# Talko_1_0.net
KiCad netlist of a schematic drawn in EAGLE
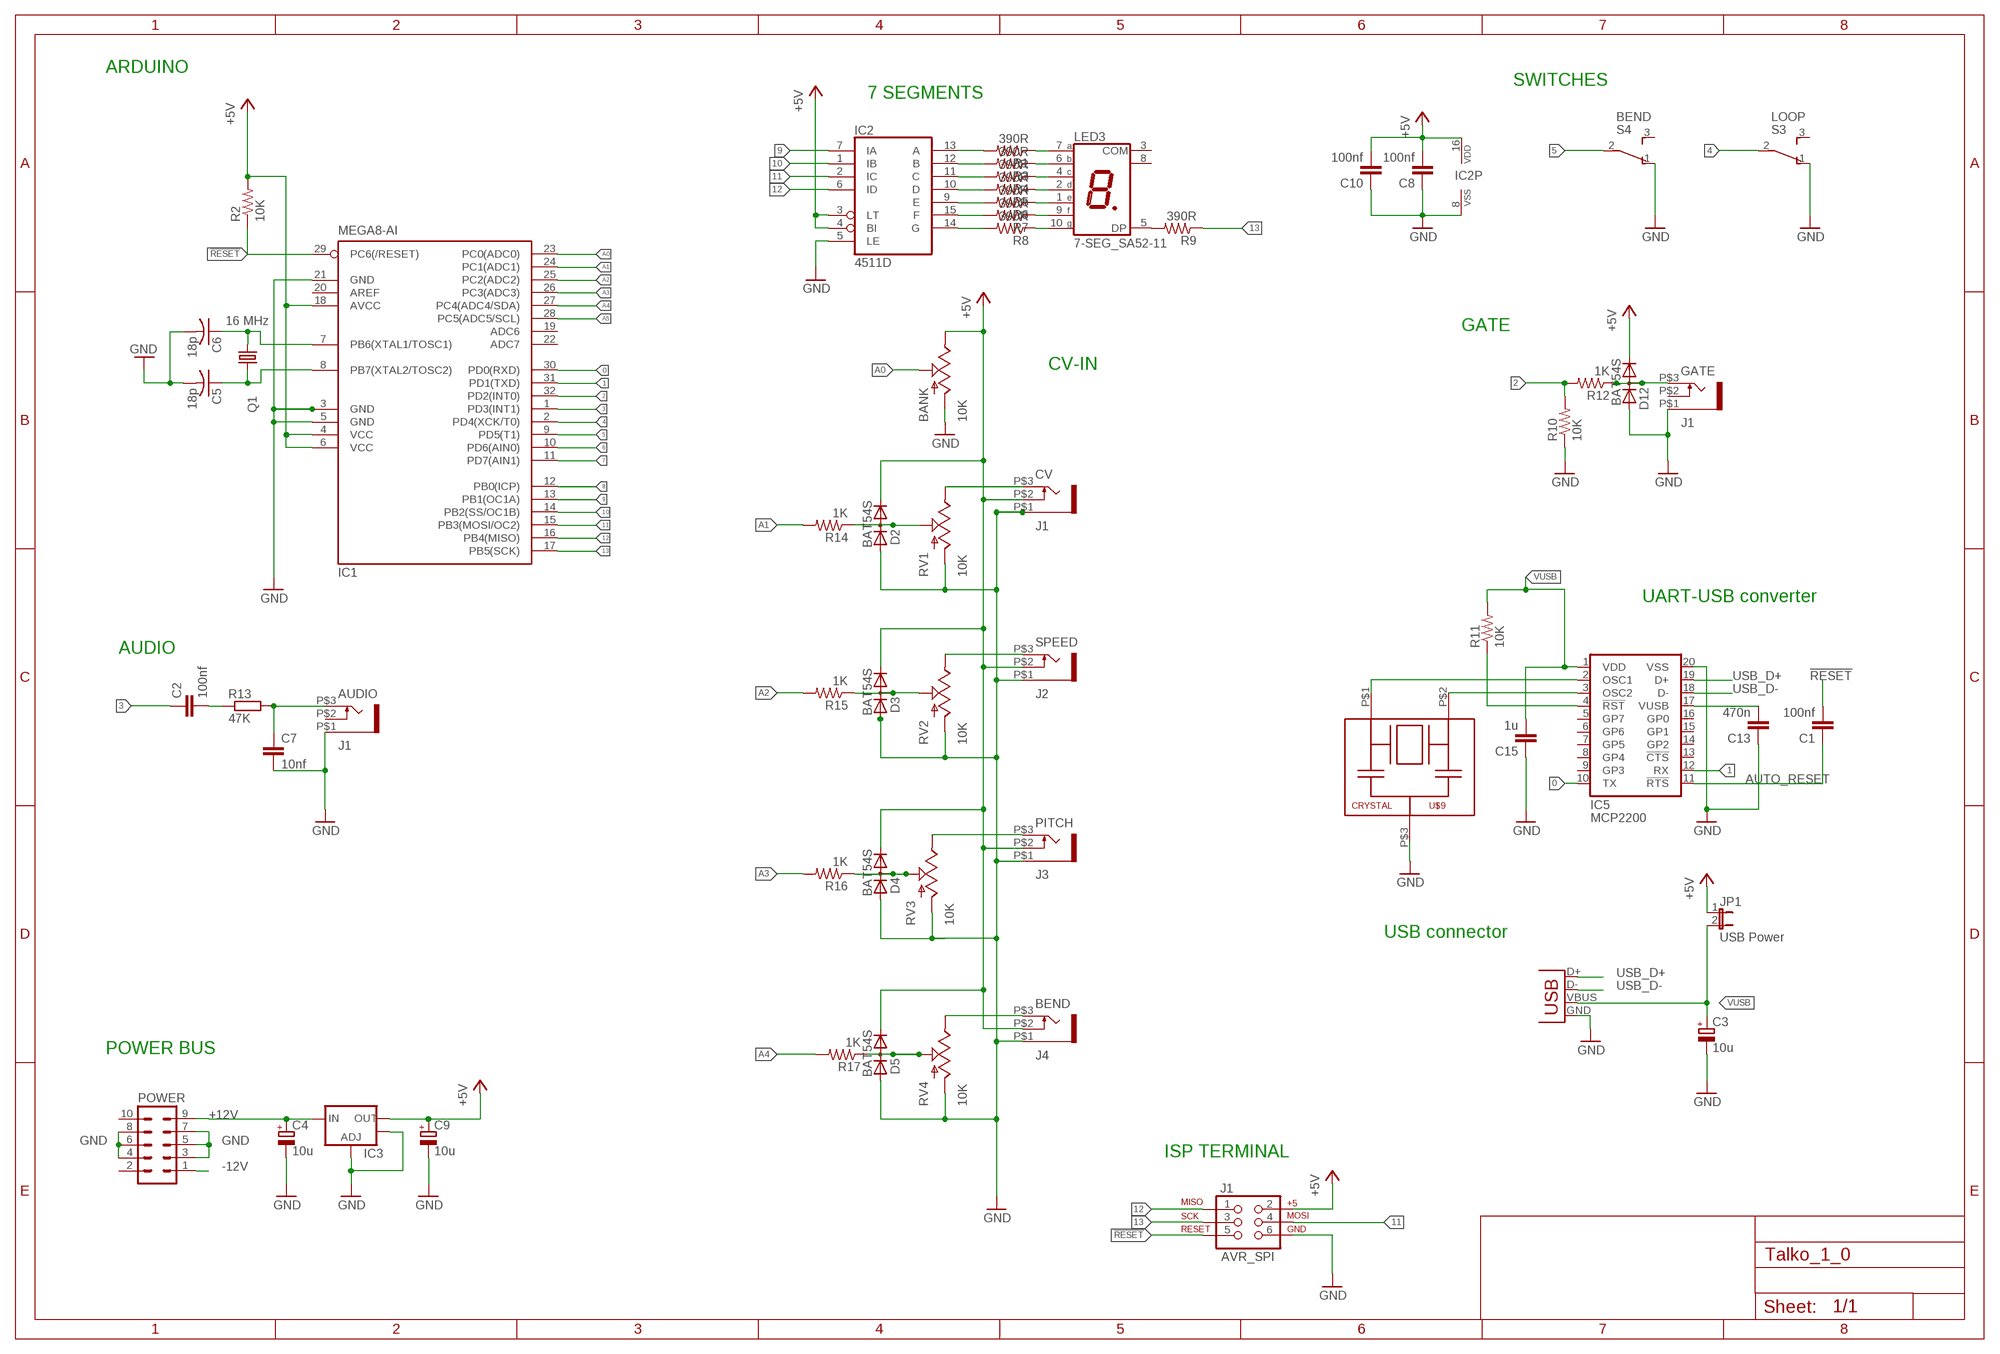
[diagram p0: schematic, sheet 1]

(export (version "E")
  (design (tool "Eeschema 10.0.6"))
  (components
    (comp (ref "AUDIO")
      (value "J1")
      (footprint "eagle-import:THONKICONN")
      (libsource (lib "eagle-import") (part "THONKICONN"))
    )
    (comp (ref "BANK")
      (value "10K")
      (footprint "eagle-import:ALPS_POT")
      (libsource (lib "eagle-import") (part "POT"))
    )
    (comp (ref "BEND")
      (value "J4")
      (footprint "eagle-import:THONKICONN")
      (libsource (lib "eagle-import") (part "THONKICONN"))
    )
    (comp (ref "C1")
      (value "100nf")
      (footprint "eagle-import:C0805")
      (libsource (lib "eagle-import") (part "C-EUC0805"))
    )
    (comp (ref "C2")
      (value "100nf")
      (footprint "eagle-import:C0805")
      (libsource (lib "eagle-import") (part "C-EUC0805"))
    )
    (comp (ref "C3")
      (value "10u")
      (footprint "eagle-import:R_2012-12R")
      (libsource (lib "eagle-import") (part "CPOL-EUR/2012-12R"))
    )
    (comp (ref "C4")
      (value "10u")
      (footprint "eagle-import:R_2012-12R")
      (libsource (lib "eagle-import") (part "CPOL-EUR/2012-12R"))
    )
    (comp (ref "C5")
      (value "18p")
      (footprint "eagle-import:C0805K")
      (libsource (lib "eagle-import") (part "C-USC0805K"))
    )
    (comp (ref "C6")
      (value "18p")
      (footprint "eagle-import:C0805K")
      (libsource (lib "eagle-import") (part "C-USC0805K"))
    )
    (comp (ref "C7")
      (value "10nf")
      (footprint "eagle-import:C0805")
      (libsource (lib "eagle-import") (part "C-EUC0805"))
    )
    (comp (ref "C8")
      (value "100nf")
      (footprint "eagle-import:C0805")
      (libsource (lib "eagle-import") (part "C-EUC0805"))
    )
    (comp (ref "C9")
      (value "10u")
      (footprint "eagle-import:R_2012-12R")
      (libsource (lib "eagle-import") (part "CPOL-EUR/2012-12R"))
    )
    (comp (ref "C10")
      (value "100nf")
      (footprint "eagle-import:C0805")
      (libsource (lib "eagle-import") (part "C-EUC0805"))
    )
    (comp (ref "C13")
      (value "470n")
      (footprint "eagle-import:0805")
      (libsource (lib "eagle-import") (part "CAP0805"))
    )
    (comp (ref "C15")
      (value "1u")
      (footprint "eagle-import:0805")
      (libsource (lib "eagle-import") (part "CAP0805"))
    )
    (comp (ref "CV")
      (value "J1")
      (footprint "eagle-import:THONKICONN")
      (libsource (lib "eagle-import") (part "THONKICONN"))
    )
    (comp (ref "D2")
      (value "BAT54S")
      (footprint "eagle-import:SOT23")
      (libsource (lib "eagle-import") (part "DIODE_2CACA-SOT23"))
    )
    (comp (ref "D3")
      (value "BAT54S")
      (footprint "eagle-import:SOT23")
      (libsource (lib "eagle-import") (part "DIODE_2CACA-SOT23"))
    )
    (comp (ref "D4")
      (value "BAT54S")
      (footprint "eagle-import:SOT23")
      (libsource (lib "eagle-import") (part "DIODE_2CACA-SOT23"))
    )
    (comp (ref "D5")
      (value "BAT54S")
      (footprint "eagle-import:SOT23")
      (libsource (lib "eagle-import") (part "DIODE_2CACA-SOT23"))
    )
    (comp (ref "D12")
      (value "BAT54S")
      (footprint "eagle-import:SOT23")
      (libsource (lib "eagle-import") (part "DIODE_2CACA-SOT23"))
    )
    (comp (ref "GATE")
      (value "J1")
      (footprint "eagle-import:THONKICONN")
      (libsource (lib "eagle-import") (part "THONKICONN"))
    )
    (comp (ref "IC1")
      (value "MEGA8-AI")
      (footprint "eagle-import:TQFP32-08")
      (fields (field (name "MPN") "ATMEGA8-16AU"))
      (libsource (lib "eagle-import") (part "MEGA8-AI"))
    )
    (comp (ref "IC2")
      (value "4511D")
      (footprint "eagle-import:SO16")
      (fields (field (name "OC_MOUSER") "863-MC14511BDG"))
      (libsource (lib "eagle-import") (part "4511D"))
    )
    (comp (ref "IC3")
      (value "V_REG_LM1117SOT223")
      (footprint "eagle-import:SOT223")
      (libsource (lib "eagle-import") (part "V_REG_LM1117SOT223"))
    )
    (comp (ref "IC5")
      (value "MCP2200")
      (footprint "eagle-import:SO20")
      (libsource (lib "eagle-import") (part "MCP2200"))
    )
    (comp (ref "J1")
      (value "AVR_SPI")
      (footprint "eagle-import:2X3_LOCK")
      (libsource (lib "eagle-import") (part "AVR_SPI_PRG_62X3_LOCK"))
    )
    (comp (ref "JP1")
      (value "USB Power")
      (footprint "eagle-import:JP1")
      (libsource (lib "eagle-import") (part "JP1E"))
    )
    (comp (ref "LED3")
      (value "7-SEG_SA52-11")
      (footprint "eagle-import:SA52-11")
      (fields (field (name "OC_FARNELL") "1168602"))
      (libsource (lib "eagle-import") (part "7-SEG_SA52-11"))
    )
    (comp (ref "PITCH")
      (value "J3")
      (footprint "eagle-import:THONKICONN")
      (libsource (lib "eagle-import") (part "THONKICONN"))
    )
    (comp (ref "POWER")
      (value "10_PIN_HEADER")
      (footprint "eagle-import:MA05-2")
      (libsource (lib "eagle-import") (part "10_PIN_HEADER"))
    )
    (comp (ref "Q1")
      (value "16 MHz")
      (footprint "eagle-import:CTS406")
      (libsource (lib "eagle-import") (part "CRYSTALCTS406"))
    )
    (comp (ref "R1")
      (value "390R")
      (footprint "eagle-import:M0805")
      (libsource (lib "eagle-import") (part "R-US_M0805"))
    )
    (comp (ref "R2")
      (value "10K")
      (footprint "eagle-import:M0805")
      (libsource (lib "eagle-import") (part "R-US_M0805"))
    )
    (comp (ref "R3")
      (value "390R")
      (footprint "eagle-import:M0805")
      (libsource (lib "eagle-import") (part "R-US_M0805"))
    )
    (comp (ref "R4")
      (value "390R")
      (footprint "eagle-import:M0805")
      (libsource (lib "eagle-import") (part "R-US_M0805"))
    )
    (comp (ref "R5")
      (value "390R")
      (footprint "eagle-import:M0805")
      (libsource (lib "eagle-import") (part "R-US_M0805"))
    )
    (comp (ref "R6")
      (value "390R")
      (footprint "eagle-import:M0805")
      (libsource (lib "eagle-import") (part "R-US_M0805"))
    )
    (comp (ref "R7")
      (value "390R")
      (footprint "eagle-import:M0805")
      (libsource (lib "eagle-import") (part "R-US_M0805"))
    )
    (comp (ref "R8")
      (value "390R")
      (footprint "eagle-import:M0805")
      (libsource (lib "eagle-import") (part "R-US_M0805"))
    )
    (comp (ref "R9")
      (value "390R")
      (footprint "eagle-import:M0805")
      (libsource (lib "eagle-import") (part "R-US_M0805"))
    )
    (comp (ref "R10")
      (value "10K")
      (footprint "eagle-import:M0805")
      (libsource (lib "eagle-import") (part "R-US_M0805"))
    )
    (comp (ref "R11")
      (value "10K")
      (footprint "eagle-import:M0805")
      (libsource (lib "eagle-import") (part "R-US_M0805"))
    )
    (comp (ref "R12")
      (value "1K")
      (footprint "eagle-import:M0805")
      (libsource (lib "eagle-import") (part "R-US_M0805"))
    )
    (comp (ref "R13")
      (value "47K")
      (footprint "eagle-import:M0805")
      (libsource (lib "eagle-import") (part "R-EU_M0805"))
    )
    (comp (ref "R14")
      (value "1K")
      (footprint "eagle-import:M0805")
      (libsource (lib "eagle-import") (part "R-US_M0805"))
    )
    (comp (ref "R15")
      (value "1K")
      (footprint "eagle-import:M0805")
      (libsource (lib "eagle-import") (part "R-US_M0805"))
    )
    (comp (ref "R16")
      (value "1K")
      (footprint "eagle-import:M0805")
      (libsource (lib "eagle-import") (part "R-US_M0805"))
    )
    (comp (ref "R17")
      (value "1K")
      (footprint "eagle-import:M0805")
      (libsource (lib "eagle-import") (part "R-US_M0805"))
    )
    (comp (ref "RV1")
      (value "10K")
      (footprint "eagle-import:ALPS_POT")
      (libsource (lib "eagle-import") (part "POT"))
    )
    (comp (ref "RV2")
      (value "10K")
      (footprint "eagle-import:ALPS_POT")
      (libsource (lib "eagle-import") (part "POT"))
    )
    (comp (ref "RV3")
      (value "10K")
      (footprint "eagle-import:ALPS_POT")
      (libsource (lib "eagle-import") (part "POT"))
    )
    (comp (ref "RV4")
      (value "10K")
      (footprint "eagle-import:ALPS_POT")
      (libsource (lib "eagle-import") (part "POT"))
    )
    (comp (ref "S3")
      (value "LOOP")
      (footprint "eagle-import:TL3XPO")
      (libsource (lib "eagle-import") (part "TL36PO"))
    )
    (comp (ref "S4")
      (value "BEND")
      (footprint "eagle-import:TL3XPO")
      (libsource (lib "eagle-import") (part "TL36PO"))
    )
    (comp (ref "SPEED")
      (value "J2")
      (footprint "eagle-import:THONKICONN")
      (libsource (lib "eagle-import") (part "THONKICONN"))
    )
    (comp (ref "U$9")
      (value "CRYSTAL")
      (footprint "eagle-import:CRYSTAL")
      (libsource (lib "eagle-import") (part "CRYSTAL"))
    )
    (comp (ref "X3")
      (value "USB")
      (footprint "eagle-import:USB-B-PTH-VERTICAL")
      (libsource (lib "eagle-import") (part "USBPTH-VERTICAL"))
    )
  )
  (nets
    (net (code "1") (name "+5V") (class "Default")
      (node (ref "BANK") (pin "P$1") (pinfunction "E_P$1") (pintype "passive"))
      (node (ref "BEND") (pin "P$2") (pinfunction "4_P$2") (pintype "passive"))
      (node (ref "C10") (pin "2") (pinfunction "2_2") (pintype "passive"))
      (node (ref "C8") (pin "2") (pinfunction "2_2") (pintype "passive"))
      (node (ref "C9") (pin "+") (pinfunction "+_+") (pintype "passive"))
      (node (ref "CV") (pin "P$2") (pinfunction "4_P$2") (pintype "passive"))
      (node (ref "D12") (pin "2") (pinfunction "C_2") (pintype "passive"))
      (node (ref "D2") (pin "2") (pinfunction "C_2") (pintype "passive"))
      (node (ref "D3") (pin "2") (pinfunction "C_2") (pintype "passive"))
      (node (ref "D4") (pin "2") (pinfunction "C_2") (pintype "passive"))
      (node (ref "D5") (pin "2") (pinfunction "C_2") (pintype "passive"))
      (node (ref "IC1") (pin "18") (pinfunction "AVCC_18") (pintype "power_in"))
      (node (ref "IC1") (pin "4") (pinfunction "VCC_4") (pintype "power_in"))
      (node (ref "IC1") (pin "6") (pinfunction "VCC_6") (pintype "power_in"))
      (node (ref "IC2") (pin "16") (pinfunction "VDD_16") (pintype "power_in"))
      (node (ref "IC2") (pin "3") (pinfunction "LT_3") (pintype "input"))
      (node (ref "IC2") (pin "4") (pinfunction "BI_4") (pintype "input"))
      (node (ref "IC3") (pin "2") (pinfunction "OUT_2") (pintype "output"))
      (node (ref "J1") (pin "2") (pinfunction "2_2") (pintype "passive"))
      (node (ref "JP1") (pin "1") (pinfunction "1_1") (pintype "passive"))
      (node (ref "PITCH") (pin "P$2") (pinfunction "4_P$2") (pintype "passive"))
      (node (ref "R2") (pin "2") (pinfunction "2_2") (pintype "passive"))
      (node (ref "SPEED") (pin "P$2") (pinfunction "4_P$2") (pintype "passive"))
    )
    (net (code "2") (name "/+12V") (class "Default")
      (node (ref "C4") (pin "+") (pinfunction "+_+") (pintype "passive"))
      (node (ref "IC3") (pin "3") (pinfunction "IN_3") (pintype "input"))
      (node (ref "POWER") (pin "9") (pinfunction "9_9") (pintype "passive"))
    )
    (net (code "3") (name "/-12V") (class "Default")
      (node (ref "POWER") (pin "1") (pinfunction "1_1") (pintype "passive"))
    )
    (net (code "4") (name "/AUTO_RESET") (class "Default")
      (node (ref "C1") (pin "1") (pinfunction "1_1") (pintype "passive"))
      (node (ref "IC5") (pin "11") (pinfunction "~{RTS}_11") (pintype "bidirectional"))
    )
    (net (code "5") (name "/USB_D+") (class "Default")
      (node (ref "IC5") (pin "19") (pinfunction "D+_19") (pintype "bidirectional"))
      (node (ref "X3") (pin "D+") (pinfunction "D+_D+") (pintype "bidirectional"))
    )
    (net (code "6") (name "/USB_D-") (class "Default")
      (node (ref "IC5") (pin "18") (pinfunction "D-_18") (pintype "bidirectional"))
      (node (ref "X3") (pin "D-") (pinfunction "D-_D-") (pintype "bidirectional"))
    )
    (net (code "7") (name "/~{RESET}") (class "Default")
      (node (ref "C1") (pin "2") (pinfunction "2_2") (pintype "passive"))
      (node (ref "IC1") (pin "29") (pinfunction "PC6(/RESET)_29") (pintype "bidirectional"))
      (node (ref "J1") (pin "5") (pinfunction "5_5") (pintype "passive"))
      (node (ref "R2") (pin "1") (pinfunction "1_1") (pintype "passive"))
    )
    (net (code "8") (name "0") (class "Default")
      (node (ref "IC1") (pin "30") (pinfunction "PD0(RXD)_30") (pintype "bidirectional"))
      (node (ref "IC5") (pin "10") (pinfunction "TX_10") (pintype "bidirectional"))
    )
    (net (code "9") (name "1") (class "Default")
      (node (ref "IC1") (pin "31") (pinfunction "PD1(TXD)_31") (pintype "bidirectional"))
      (node (ref "IC5") (pin "12") (pinfunction "RX_12") (pintype "bidirectional"))
    )
    (net (code "10") (name "2") (class "Default")
      (node (ref "IC1") (pin "32") (pinfunction "PD2(INT0)_32") (pintype "bidirectional"))
      (node (ref "R10") (pin "2") (pinfunction "2_2") (pintype "passive"))
      (node (ref "R12") (pin "2") (pinfunction "2_2") (pintype "passive"))
    )
    (net (code "11") (name "3") (class "Default")
      (node (ref "C2") (pin "1") (pinfunction "1_1") (pintype "passive"))
      (node (ref "IC1") (pin "1") (pinfunction "PD3(INT1)_1") (pintype "bidirectional"))
    )
    (net (code "12") (name "4") (class "Default")
      (node (ref "IC1") (pin "2") (pinfunction "PD4(XCK/T0)_2") (pintype "bidirectional"))
      (node (ref "S3") (pin "2") (pinfunction "P_2") (pintype "passive"))
    )
    (net (code "13") (name "5") (class "Default")
      (node (ref "IC1") (pin "9") (pinfunction "PD5(T1)_9") (pintype "bidirectional"))
      (node (ref "S4") (pin "2") (pinfunction "P_2") (pintype "passive"))
    )
    (net (code "14") (name "6") (class "Default")
      (node (ref "IC1") (pin "10") (pinfunction "PD6(AIN0)_10") (pintype "bidirectional"))
    )
    (net (code "15") (name "7") (class "Default")
      (node (ref "IC1") (pin "11") (pinfunction "PD7(AIN1)_11") (pintype "bidirectional"))
    )
    (net (code "16") (name "8") (class "Default")
      (node (ref "IC1") (pin "12") (pinfunction "PB0(ICP)_12") (pintype "bidirectional"))
    )
    (net (code "17") (name "9") (class "Default")
      (node (ref "IC1") (pin "13") (pinfunction "PB1(OC1A)_13") (pintype "bidirectional"))
      (node (ref "IC2") (pin "7") (pinfunction "IA_7") (pintype "input"))
    )
    (net (code "18") (name "10") (class "Default")
      (node (ref "IC1") (pin "14") (pinfunction "PB2(SS/OC1B)_14") (pintype "bidirectional"))
      (node (ref "IC2") (pin "1") (pinfunction "IB_1") (pintype "input"))
    )
    (net (code "19") (name "11") (class "Default")
      (node (ref "IC1") (pin "15") (pinfunction "PB3(MOSI/OC2)_15") (pintype "bidirectional"))
      (node (ref "IC2") (pin "2") (pinfunction "IC_2") (pintype "input"))
      (node (ref "J1") (pin "4") (pinfunction "4_4") (pintype "passive"))
    )
    (net (code "20") (name "12") (class "Default")
      (node (ref "IC1") (pin "16") (pinfunction "PB4(MISO)_16") (pintype "bidirectional"))
      (node (ref "IC2") (pin "6") (pinfunction "ID_6") (pintype "input"))
      (node (ref "J1") (pin "1") (pinfunction "1_1") (pintype "passive"))
    )
    (net (code "21") (name "13") (class "Default")
      (node (ref "IC1") (pin "17") (pinfunction "PB5(SCK)_17") (pintype "bidirectional"))
      (node (ref "J1") (pin "3") (pinfunction "3_3") (pintype "passive"))
      (node (ref "R9") (pin "1") (pinfunction "1_1") (pintype "passive"))
    )
    (net (code "22") (name "A0") (class "Default")
      (node (ref "BANK") (pin "P$2") (pinfunction "S_P$2") (pintype "passive"))
      (node (ref "IC1") (pin "23") (pinfunction "PC0(ADC0)_23") (pintype "bidirectional"))
    )
    (net (code "23") (name "A1") (class "Default")
      (node (ref "IC1") (pin "24") (pinfunction "PC1(ADC1)_24") (pintype "bidirectional"))
      (node (ref "R14") (pin "2") (pinfunction "2_2") (pintype "passive"))
    )
    (net (code "24") (name "A2") (class "Default")
      (node (ref "IC1") (pin "25") (pinfunction "PC2(ADC2)_25") (pintype "bidirectional"))
      (node (ref "R15") (pin "2") (pinfunction "2_2") (pintype "passive"))
    )
    (net (code "25") (name "A3") (class "Default")
      (node (ref "IC1") (pin "26") (pinfunction "PC3(ADC3)_26") (pintype "bidirectional"))
      (node (ref "R16") (pin "2") (pinfunction "2_2") (pintype "passive"))
    )
    (net (code "26") (name "A4") (class "Default")
      (node (ref "IC1") (pin "27") (pinfunction "PC4(ADC4/SDA)_27") (pintype "bidirectional"))
      (node (ref "R17") (pin "2") (pinfunction "2_2") (pintype "passive"))
    )
    (net (code "27") (name "A5") (class "Default")
      (node (ref "IC1") (pin "28") (pinfunction "PC5(ADC5/SCL)_28") (pintype "bidirectional"))
    )
    (net (code "28") (name "GND") (class "Default")
      (node (ref "AUDIO") (pin "P$1") (pinfunction "5_P$1") (pintype "passive"))
      (node (ref "BANK") (pin "P$3") (pinfunction "A_P$3") (pintype "passive"))
      (node (ref "BEND") (pin "P$1") (pinfunction "5_P$1") (pintype "passive"))
      (node (ref "C10") (pin "1") (pinfunction "1_1") (pintype "passive"))
      (node (ref "C13") (pin "1") (pinfunction "1_1") (pintype "passive"))
      (node (ref "C15") (pin "1") (pinfunction "1_1") (pintype "passive"))
      (node (ref "C3") (pin "-") (pinfunction "-_-") (pintype "passive"))
      (node (ref "C4") (pin "-") (pinfunction "-_-") (pintype "passive"))
      (node (ref "C5") (pin "2") (pinfunction "2_2") (pintype "passive"))
      (node (ref "C6") (pin "2") (pinfunction "2_2") (pintype "passive"))
      (node (ref "C7") (pin "2") (pinfunction "2_2") (pintype "passive"))
      (node (ref "C8") (pin "1") (pinfunction "1_1") (pintype "passive"))
      (node (ref "C9") (pin "-") (pinfunction "-_-") (pintype "passive"))
      (node (ref "CV") (pin "P$1") (pinfunction "5_P$1") (pintype "passive"))
      (node (ref "D12") (pin "1") (pinfunction "A_1") (pintype "passive"))
      (node (ref "D2") (pin "1") (pinfunction "A_1") (pintype "passive"))
      (node (ref "D3") (pin "1") (pinfunction "A_1") (pintype "passive"))
      (node (ref "D4") (pin "1") (pinfunction "A_1") (pintype "passive"))
      (node (ref "D5") (pin "1") (pinfunction "A_1") (pintype "passive"))
      (node (ref "GATE") (pin "P$1") (pinfunction "5_P$1") (pintype "passive"))
      (node (ref "IC1") (pin "21") (pinfunction "GND_21") (pintype "power_in"))
      (node (ref "IC1") (pin "3") (pinfunction "GND_3") (pintype "power_in"))
      (node (ref "IC1") (pin "5") (pinfunction "GND_5") (pintype "power_in"))
      (node (ref "IC2") (pin "5") (pinfunction "LE_5") (pintype "input"))
      (node (ref "IC2") (pin "8") (pinfunction "VSS_8") (pintype "power_in"))
      (node (ref "IC3") (pin "1") (pinfunction "ADJ_1") (pintype "input"))
      (node (ref "IC3") (pin "4") (pinfunction "OUT_4") (pintype "output"))
      (node (ref "IC5") (pin "20") (pinfunction "VSS_20") (pintype "power_in"))
      (node (ref "J1") (pin "6") (pinfunction "6_6") (pintype "passive"))
      (node (ref "PITCH") (pin "P$1") (pinfunction "5_P$1") (pintype "passive"))
      (node (ref "POWER") (pin "3") (pinfunction "3_3") (pintype "passive"))
      (node (ref "POWER") (pin "4") (pinfunction "4_4") (pintype "passive"))
      (node (ref "POWER") (pin "5") (pinfunction "5_5") (pintype "passive"))
      (node (ref "POWER") (pin "6") (pinfunction "6_6") (pintype "passive"))
      (node (ref "POWER") (pin "7") (pinfunction "7_7") (pintype "passive"))
      (node (ref "POWER") (pin "8") (pinfunction "8_8") (pintype "passive"))
      (node (ref "R10") (pin "1") (pinfunction "1_1") (pintype "passive"))
      (node (ref "RV1") (pin "P$3") (pinfunction "A_P$3") (pintype "passive"))
      (node (ref "RV2") (pin "P$3") (pinfunction "A_P$3") (pintype "passive"))
      (node (ref "RV3") (pin "P$3") (pinfunction "A_P$3") (pintype "passive"))
      (node (ref "RV4") (pin "P$3") (pinfunction "A_P$3") (pintype "passive"))
      (node (ref "S3") (pin "1") (pinfunction "O_1") (pintype "passive"))
      (node (ref "S4") (pin "1") (pinfunction "O_1") (pintype "passive"))
      (node (ref "SPEED") (pin "P$1") (pinfunction "5_P$1") (pintype "passive"))
      (node (ref "U$9") (pin "P$3") (pinfunction "3_P$3") (pintype "bidirectional"))
      (node (ref "X3") (pin "GND") (pinfunction "GND_GND") (pintype "bidirectional"))
    )
    (net (code "29") (name "Net-(AUDIO-3)") (class "Default")
      (node (ref "AUDIO") (pin "P$3") (pinfunction "3_P$3") (pintype "passive"))
      (node (ref "C7") (pin "1") (pinfunction "1_1") (pintype "passive"))
      (node (ref "R13") (pin "2") (pinfunction "2_2") (pintype "passive"))
    )
    (net (code "30") (name "Net-(BEND-3)") (class "Default")
      (node (ref "BEND") (pin "P$3") (pinfunction "3_P$3") (pintype "passive"))
      (node (ref "RV4") (pin "P$1") (pinfunction "E_P$1") (pintype "passive"))
    )
    (net (code "31") (name "Net-(C2-Pad2)") (class "Default")
      (node (ref "C2") (pin "2") (pinfunction "2_2") (pintype "passive"))
      (node (ref "R13") (pin "1") (pinfunction "1_1") (pintype "passive"))
    )
    (net (code "32") (name "Net-(CV-3)") (class "Default")
      (node (ref "CV") (pin "P$3") (pinfunction "3_P$3") (pintype "passive"))
      (node (ref "RV1") (pin "P$1") (pinfunction "E_P$1") (pintype "passive"))
    )
    (net (code "33") (name "Net-(D2-AC)") (class "Default")
      (node (ref "D2") (pin "3") (pinfunction "AC_3") (pintype "passive"))
      (node (ref "R14") (pin "1") (pinfunction "1_1") (pintype "passive"))
      (node (ref "RV1") (pin "P$2") (pinfunction "S_P$2") (pintype "passive"))
    )
    (net (code "34") (name "Net-(D3-AC)") (class "Default")
      (node (ref "D3") (pin "3") (pinfunction "AC_3") (pintype "passive"))
      (node (ref "R15") (pin "1") (pinfunction "1_1") (pintype "passive"))
      (node (ref "RV2") (pin "P$2") (pinfunction "S_P$2") (pintype "passive"))
    )
    (net (code "35") (name "Net-(D4-AC)") (class "Default")
      (node (ref "D4") (pin "3") (pinfunction "AC_3") (pintype "passive"))
      (node (ref "R16") (pin "1") (pinfunction "1_1") (pintype "passive"))
      (node (ref "RV3") (pin "P$2") (pinfunction "S_P$2") (pintype "passive"))
    )
    (net (code "36") (name "Net-(D5-AC)") (class "Default")
      (node (ref "D5") (pin "3") (pinfunction "AC_3") (pintype "passive"))
      (node (ref "R17") (pin "1") (pinfunction "1_1") (pintype "passive"))
      (node (ref "RV4") (pin "P$2") (pinfunction "S_P$2") (pintype "passive"))
    )
    (net (code "37") (name "Net-(D12-AC)") (class "Default")
      (node (ref "D12") (pin "3") (pinfunction "AC_3") (pintype "passive"))
      (node (ref "GATE") (pin "P$3") (pinfunction "3_P$3") (pintype "passive"))
      (node (ref "R12") (pin "1") (pinfunction "1_1") (pintype "passive"))
    )
    (net (code "38") (name "Net-(IC1-PB6(XTAL1{slash}TOSC1))") (class "Default")
      (node (ref "C6") (pin "1") (pinfunction "1_1") (pintype "passive"))
      (node (ref "IC1") (pin "7") (pinfunction "PB6(XTAL1/TOSC1)_7") (pintype "bidirectional"))
      (node (ref "Q1") (pin "3") (pinfunction "2_3") (pintype "passive"))
    )
    (net (code "39") (name "Net-(IC1-PB7(XTAL2{slash}TOSC2))") (class "Default")
      (node (ref "C5") (pin "1") (pinfunction "1_1") (pintype "passive"))
      (node (ref "IC1") (pin "8") (pinfunction "PB7(XTAL2/TOSC2)_8") (pintype "bidirectional"))
      (node (ref "Q1") (pin "1") (pinfunction "1_1") (pintype "passive"))
    )
    (net (code "40") (name "Net-(IC2A-A)") (class "Default")
      (node (ref "IC2") (pin "13") (pinfunction "A_13") (pintype "output"))
      (node (ref "R1") (pin "2") (pinfunction "2_2") (pintype "passive"))
    )
    (net (code "41") (name "Net-(IC2A-B)") (class "Default")
      (node (ref "IC2") (pin "12") (pinfunction "B_12") (pintype "output"))
      (node (ref "R3") (pin "2") (pinfunction "2_2") (pintype "passive"))
    )
    (net (code "42") (name "Net-(IC2A-C)") (class "Default")
      (node (ref "IC2") (pin "11") (pinfunction "C_11") (pintype "output"))
      (node (ref "R4") (pin "2") (pinfunction "2_2") (pintype "passive"))
    )
    (net (code "43") (name "Net-(IC2A-D)") (class "Default")
      (node (ref "IC2") (pin "10") (pinfunction "D_10") (pintype "output"))
      (node (ref "R5") (pin "2") (pinfunction "2_2") (pintype "passive"))
    )
    (net (code "44") (name "Net-(IC2A-E)") (class "Default")
      (node (ref "IC2") (pin "9") (pinfunction "E_9") (pintype "output"))
      (node (ref "R6") (pin "2") (pinfunction "2_2") (pintype "passive"))
    )
    (net (code "45") (name "Net-(IC2A-F)") (class "Default")
      (node (ref "IC2") (pin "15") (pinfunction "F_15") (pintype "output"))
      (node (ref "R7") (pin "2") (pinfunction "2_2") (pintype "passive"))
    )
    (net (code "46") (name "Net-(IC2A-G)") (class "Default")
      (node (ref "IC2") (pin "14") (pinfunction "G_14") (pintype "output"))
      (node (ref "R8") (pin "2") (pinfunction "2_2") (pintype "passive"))
    )
    (net (code "47") (name "Net-(IC5-OSC1)") (class "Default")
      (node (ref "IC5") (pin "2") (pinfunction "OSC1_2") (pintype "bidirectional"))
      (node (ref "U$9") (pin "P$1") (pinfunction "1_P$1") (pintype "bidirectional"))
    )
    (net (code "48") (name "Net-(IC5-OSC2)") (class "Default")
      (node (ref "IC5") (pin "3") (pinfunction "OSC2_3") (pintype "bidirectional"))
      (node (ref "U$9") (pin "P$2") (pinfunction "2_P$2") (pintype "bidirectional"))
    )
    (net (code "49") (name "Net-(IC5-VUSB)") (class "Default")
      (node (ref "C13") (pin "2") (pinfunction "2_2") (pintype "passive"))
      (node (ref "IC5") (pin "17") (pinfunction "VUSB_17") (pintype "bidirectional"))
    )
    (net (code "50") (name "Net-(IC5-~{RST})") (class "Default")
      (node (ref "IC5") (pin "4") (pinfunction "~{RST}_4") (pintype "bidirectional"))
      (node (ref "R11") (pin "1") (pinfunction "1_1") (pintype "passive"))
    )
    (net (code "51") (name "Net-(LED3-A)") (class "Default")
      (node (ref "LED3") (pin "7") (pinfunction "A_7") (pintype "passive"))
      (node (ref "R1") (pin "1") (pinfunction "1_1") (pintype "passive"))
    )
    (net (code "52") (name "Net-(LED3-B)") (class "Default")
      (node (ref "LED3") (pin "6") (pinfunction "B_6") (pintype "passive"))
      (node (ref "R3") (pin "1") (pinfunction "1_1") (pintype "passive"))
    )
    (net (code "53") (name "Net-(LED3-C)") (class "Default")
      (node (ref "LED3") (pin "4") (pinfunction "C_4") (pintype "passive"))
      (node (ref "R4") (pin "1") (pinfunction "1_1") (pintype "passive"))
    )
    (net (code "54") (name "Net-(LED3-D)") (class "Default")
      (node (ref "LED3") (pin "2") (pinfunction "D_2") (pintype "passive"))
      (node (ref "R5") (pin "1") (pinfunction "1_1") (pintype "passive"))
    )
    (net (code "55") (name "Net-(LED3-DP)") (class "Default")
      (node (ref "LED3") (pin "5") (pinfunction "DP_5") (pintype "passive"))
      (node (ref "R9") (pin "2") (pinfunction "2_2") (pintype "passive"))
    )
    (net (code "56") (name "Net-(LED3-E)") (class "Default")
      (node (ref "LED3") (pin "1") (pinfunction "E_1") (pintype "passive"))
      (node (ref "R6") (pin "1") (pinfunction "1_1") (pintype "passive"))
    )
    (net (code "57") (name "Net-(LED3-F)") (class "Default")
      (node (ref "LED3") (pin "9") (pinfunction "F_9") (pintype "passive"))
      (node (ref "R7") (pin "1") (pinfunction "1_1") (pintype "passive"))
    )
    (net (code "58") (name "Net-(LED3-G)") (class "Default")
      (node (ref "LED3") (pin "10") (pinfunction "G_10") (pintype "passive"))
      (node (ref "R8") (pin "1") (pinfunction "1_1") (pintype "passive"))
    )
    (net (code "59") (name "Net-(PITCH-3)") (class "Default")
      (node (ref "PITCH") (pin "P$3") (pinfunction "3_P$3") (pintype "passive"))
      (node (ref "RV3") (pin "P$1") (pinfunction "E_P$1") (pintype "passive"))
    )
    (net (code "60") (name "Net-(RV2-E)") (class "Default")
      (node (ref "RV2") (pin "P$1") (pinfunction "E_P$1") (pintype "passive"))
      (node (ref "SPEED") (pin "P$3") (pinfunction "3_P$3") (pintype "passive"))
    )
    (net (code "61") (name "VUSB") (class "Default")
      (node (ref "C15") (pin "2") (pinfunction "2_2") (pintype "passive"))
      (node (ref "C3") (pin "+") (pinfunction "+_+") (pintype "passive"))
      (node (ref "IC5") (pin "1") (pinfunction "VDD_1") (pintype "power_in"))
      (node (ref "JP1") (pin "2") (pinfunction "2_2") (pintype "passive"))
      (node (ref "R11") (pin "2") (pinfunction "2_2") (pintype "passive"))
      (node (ref "X3") (pin "VBUS") (pinfunction "VBUS_VBUS") (pintype "bidirectional"))
    )
    (net (code "62") (name "unconnected-(AUDIO-4-PadP$2)") (class "Default")
      (node (ref "AUDIO") (pin "P$2") (pinfunction "4_P$2") (pintype "passive"))
    )
    (net (code "63") (name "unconnected-(GATE-4-PadP$2)") (class "Default")
      (node (ref "GATE") (pin "P$2") (pinfunction "4_P$2") (pintype "passive"))
    )
    (net (code "64") (name "unconnected-(IC1-ADC6-Pad19)") (class "Default")
      (node (ref "IC1") (pin "19") (pinfunction "ADC6_19") (pintype "bidirectional"))
    )
    (net (code "65") (name "unconnected-(IC1-ADC7-Pad22)") (class "Default")
      (node (ref "IC1") (pin "22") (pinfunction "ADC7_22") (pintype "bidirectional"))
    )
    (net (code "66") (name "unconnected-(IC1-AREF-Pad20)") (class "Default")
      (node (ref "IC1") (pin "20") (pinfunction "AREF_20") (pintype "passive"))
    )
    (net (code "67") (name "unconnected-(IC5-GP0-Pad16)") (class "Default")
      (node (ref "IC5") (pin "16") (pinfunction "GP0_16") (pintype "bidirectional"))
    )
    (net (code "68") (name "unconnected-(IC5-GP1-Pad15)") (class "Default")
      (node (ref "IC5") (pin "15") (pinfunction "GP1_15") (pintype "bidirectional"))
    )
    (net (code "69") (name "unconnected-(IC5-GP2-Pad14)") (class "Default")
      (node (ref "IC5") (pin "14") (pinfunction "GP2_14") (pintype "bidirectional"))
    )
    (net (code "70") (name "unconnected-(IC5-GP3-Pad9)") (class "Default")
      (node (ref "IC5") (pin "9") (pinfunction "GP3_9") (pintype "bidirectional"))
    )
    (net (code "71") (name "unconnected-(IC5-GP4-Pad8)") (class "Default")
      (node (ref "IC5") (pin "8") (pinfunction "GP4_8") (pintype "bidirectional"))
    )
    (net (code "72") (name "unconnected-(IC5-GP5-Pad7)") (class "Default")
      (node (ref "IC5") (pin "7") (pinfunction "GP5_7") (pintype "bidirectional"))
    )
    (net (code "73") (name "unconnected-(IC5-GP6-Pad6)") (class "Default")
      (node (ref "IC5") (pin "6") (pinfunction "GP6_6") (pintype "bidirectional"))
    )
    (net (code "74") (name "unconnected-(IC5-GP7-Pad5)") (class "Default")
      (node (ref "IC5") (pin "5") (pinfunction "GP7_5") (pintype "bidirectional"))
    )
    (net (code "75") (name "unconnected-(IC5-~{CTS}-Pad13)") (class "Default")
      (node (ref "IC5") (pin "13") (pinfunction "~{CTS}_13") (pintype "bidirectional"))
    )
    (net (code "76") (name "unconnected-(LED3-COM-Pad3)") (class "Default")
      (node (ref "LED3") (pin "3") (pinfunction "COM_3") (pintype "passive"))
    )
    (net (code "77") (name "unconnected-(LED3-COM-Pad8)") (class "Default")
      (node (ref "LED3") (pin "8") (pinfunction "COM_8") (pintype "passive"))
    )
    (net (code "78") (name "unconnected-(POWER-Pad2)") (class "Default")
      (node (ref "POWER") (pin "2") (pinfunction "2_2") (pintype "passive"))
    )
    (net (code "79") (name "unconnected-(POWER-Pad10)") (class "Default")
      (node (ref "POWER") (pin "10") (pinfunction "10_10") (pintype "passive"))
    )
    (net (code "80") (name "unconnected-(S3-S-Pad3)") (class "Default")
      (node (ref "S3") (pin "3") (pinfunction "S_3") (pintype "passive"))
    )
    (net (code "81") (name "unconnected-(S4-S-Pad3)") (class "Default")
      (node (ref "S4") (pin "3") (pinfunction "S_3") (pintype "passive"))
    )
  )
)
